# mount.net
KiCad netlist of a schematic drawn in EAGLE
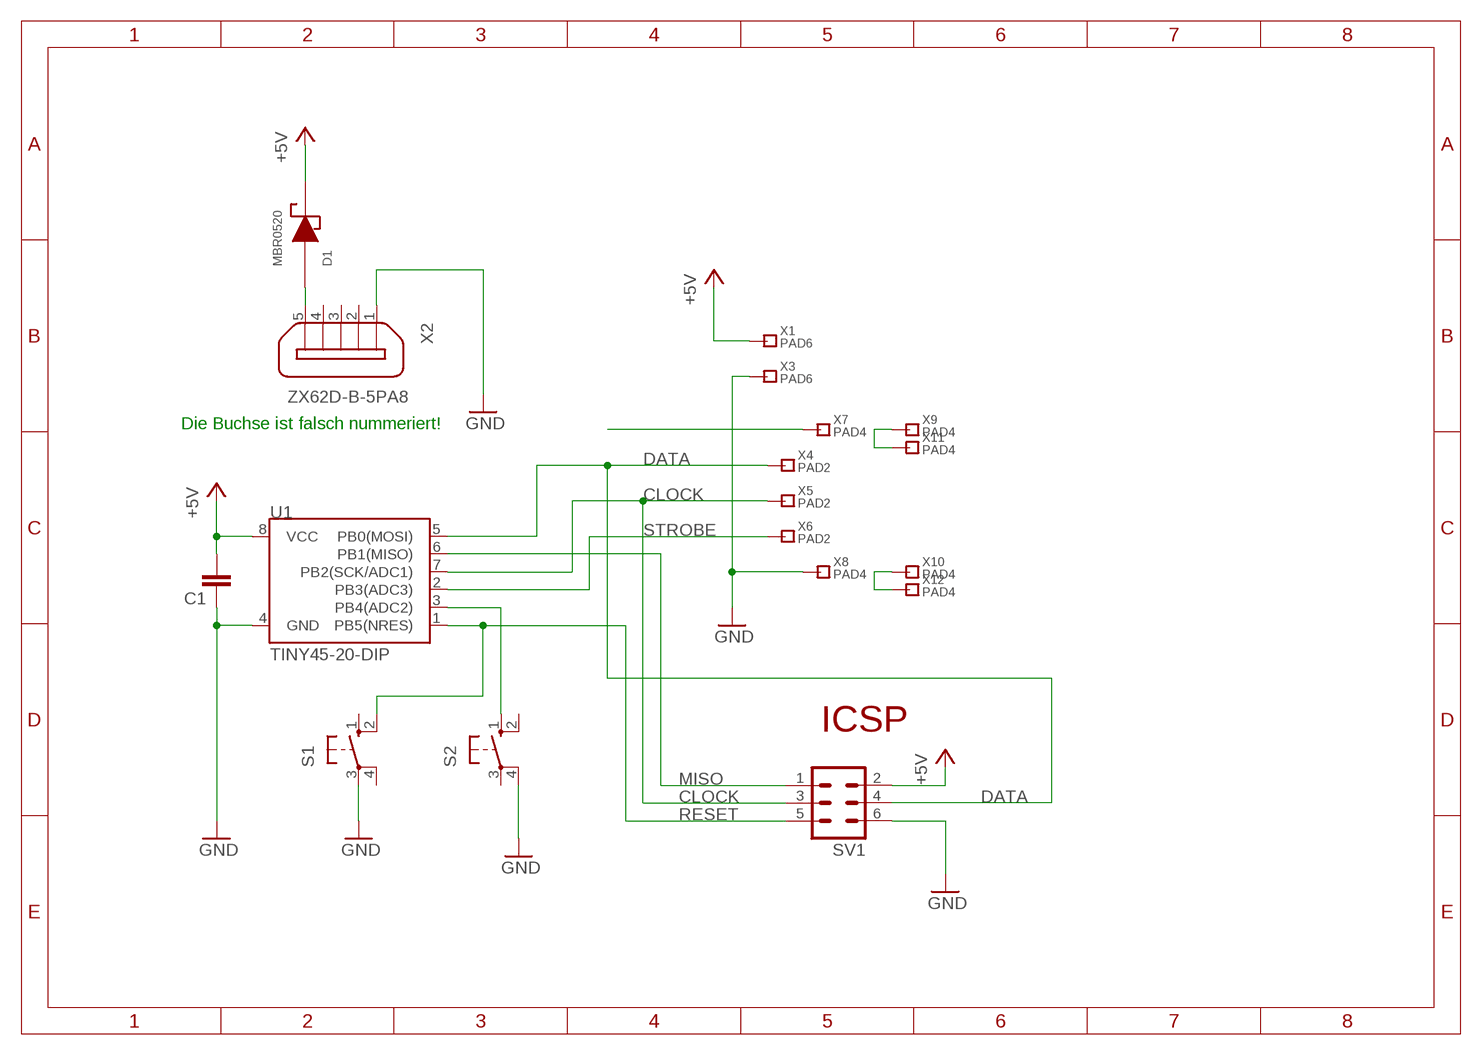
[diagram p0: schematic, sheet 1]

(export (version "E")
  (design (tool "Eeschema 10.0.6"))
  (components
    (comp (ref "C1")
      (value "C-EUC0805")
      (footprint "eagle-import:C0805")
      (libsource (lib "eagle-import") (part "C-EUC0805"))
    )
    (comp (ref "D1")
      (value "MBR0520")
      (footprint "eagle-import:SOD-123")
      (libsource (lib "eagle-import") (part "MBR0520"))
    )
    (comp (ref "S1")
      (value "10-XX")
      (footprint "eagle-import:B3F-10XX")
      (fields (field (name "MPN") "B3F-1000"))
      (libsource (lib "eagle-import") (part "10-XX"))
    )
    (comp (ref "S2")
      (value "10-XX")
      (footprint "eagle-import:B3F-10XX")
      (fields (field (name "MPN") "B3F-1000"))
      (libsource (lib "eagle-import") (part "10-XX"))
    )
    (comp (ref "SV1")
      (value "MA03-2")
      (footprint "eagle-import:MA03-2")
      (libsource (lib "eagle-import") (part "MA03-2"))
    )
    (comp (ref "U1")
      (value "TINY45-20-DIP")
      (footprint "eagle-import:DIP08_MCU")
      (libsource (lib "eagle-import") (part "ATTINY45TINY45-20-DIP"))
    )
    (comp (ref "X1")
      (value "PAD6")
      (footprint "eagle-import:SMDPAD")
      (libsource (lib "eagle-import") (part "PAD6"))
    )
    (comp (ref "X2")
      (value "ZX62D-B-5PA8")
      (footprint "eagle-import:ZX62D-B-5PA8")
      (fields (field (name "MF") "Hirose"))
      (libsource (lib "eagle-import") (part "ZX62D-B-5PA8"))
    )
    (comp (ref "X3")
      (value "PAD6")
      (footprint "eagle-import:SMDPAD")
      (libsource (lib "eagle-import") (part "PAD6"))
    )
    (comp (ref "X4")
      (value "PAD2")
      (footprint "eagle-import:SMDPAD_S")
      (libsource (lib "eagle-import") (part "PAD2"))
    )
    (comp (ref "X5")
      (value "PAD2")
      (footprint "eagle-import:SMDPAD_S")
      (libsource (lib "eagle-import") (part "PAD2"))
    )
    (comp (ref "X6")
      (value "PAD2")
      (footprint "eagle-import:SMDPAD_S")
      (libsource (lib "eagle-import") (part "PAD2"))
    )
    (comp (ref "X7")
      (value "PAD4")
      (footprint "eagle-import:SMDPAD_M")
      (libsource (lib "eagle-import") (part "PAD4"))
    )
    (comp (ref "X8")
      (value "PAD4")
      (footprint "eagle-import:SMDPAD_M")
      (libsource (lib "eagle-import") (part "PAD4"))
    )
    (comp (ref "X9")
      (value "PAD4")
      (footprint "eagle-import:SMDPAD_M")
      (libsource (lib "eagle-import") (part "PAD4"))
    )
    (comp (ref "X10")
      (value "PAD4")
      (footprint "eagle-import:SMDPAD_M")
      (libsource (lib "eagle-import") (part "PAD4"))
    )
    (comp (ref "X11")
      (value "PAD4")
      (footprint "eagle-import:SMDPAD_M")
      (libsource (lib "eagle-import") (part "PAD4"))
    )
    (comp (ref "X12")
      (value "PAD4")
      (footprint "eagle-import:SMDPAD_M")
      (libsource (lib "eagle-import") (part "PAD4"))
    )
  )
  (nets
    (net (code "1") (name "+5V") (class "Default")
      (node (ref "C1") (pin "2") (pinfunction "2_2") (pintype "passive"))
      (node (ref "D1") (pin "1") (pinfunction "CA_1") (pintype "passive"))
      (node (ref "SV1") (pin "2") (pinfunction "2_2") (pintype "passive"))
      (node (ref "U1") (pin "8") (pinfunction "VCC_8") (pintype "bidirectional"))
      (node (ref "X1") (pin "P$1") (pinfunction "P$1_P$1") (pintype "bidirectional"))
    )
    (net (code "2") (name "/CLOCK") (class "Default")
      (node (ref "SV1") (pin "3") (pinfunction "3_3") (pintype "passive"))
      (node (ref "U1") (pin "7") (pinfunction "PB2(SCK/ADC1)_7") (pintype "bidirectional"))
      (node (ref "X5") (pin "P$1") (pinfunction "P$1_P$1") (pintype "bidirectional"))
    )
    (net (code "3") (name "/DATA") (class "Default")
      (node (ref "SV1") (pin "4") (pinfunction "4_4") (pintype "passive"))
      (node (ref "U1") (pin "5") (pinfunction "PB0(MOSI)_5") (pintype "bidirectional"))
      (node (ref "X4") (pin "P$1") (pinfunction "P$1_P$1") (pintype "bidirectional"))
    )
    (net (code "4") (name "/MISO") (class "Default")
      (node (ref "SV1") (pin "1") (pinfunction "1_1") (pintype "passive"))
      (node (ref "U1") (pin "6") (pinfunction "PB1(MISO)_6") (pintype "bidirectional"))
    )
    (net (code "5") (name "/RESET") (class "Default")
      (node (ref "S1") (pin "2") (pinfunction "S1_2") (pintype "passive"))
      (node (ref "SV1") (pin "5") (pinfunction "5_5") (pintype "passive"))
      (node (ref "U1") (pin "1") (pinfunction "PB5(NRES)_1") (pintype "bidirectional"))
    )
    (net (code "6") (name "/STROBE") (class "Default")
      (node (ref "U1") (pin "2") (pinfunction "PB3(ADC3)_2") (pintype "bidirectional"))
      (node (ref "X6") (pin "P$1") (pinfunction "P$1_P$1") (pintype "bidirectional"))
    )
    (net (code "7") (name "GND") (class "Default")
      (node (ref "C1") (pin "1") (pinfunction "1_1") (pintype "passive"))
      (node (ref "S1") (pin "3") (pinfunction "P_3") (pintype "passive"))
      (node (ref "S2") (pin "4") (pinfunction "P1_4") (pintype "passive"))
      (node (ref "SV1") (pin "6") (pinfunction "6_6") (pintype "passive"))
      (node (ref "U1") (pin "4") (pinfunction "GND_4") (pintype "bidirectional"))
      (node (ref "X2") (pin "1") (pinfunction "1_1") (pintype "passive"))
      (node (ref "X3") (pin "P$1") (pinfunction "P$1_P$1") (pintype "bidirectional"))
      (node (ref "X8") (pin "P$1") (pinfunction "P$1_P$1") (pintype "bidirectional"))
    )
    (net (code "8") (name "Net-(D1-AN)") (class "Default")
      (node (ref "D1") (pin "2") (pinfunction "AN_2") (pintype "passive"))
      (node (ref "X2") (pin "5") (pinfunction "5_5") (pintype "passive"))
    )
    (net (code "9") (name "Net-(S2-S)") (class "Default")
      (node (ref "S2") (pin "1") (pinfunction "S_1") (pintype "passive"))
      (node (ref "U1") (pin "3") (pinfunction "PB4(ADC2)_3") (pintype "bidirectional"))
    )
    (net (code "10") (name "Net-(X10-PadP$1)") (class "Default")
      (node (ref "X10") (pin "P$1") (pinfunction "P$1_P$1") (pintype "bidirectional"))
      (node (ref "X12") (pin "P$1") (pinfunction "P$1_P$1") (pintype "bidirectional"))
    )
    (net (code "11") (name "Net-(X11-PadP$1)") (class "Default")
      (node (ref "X11") (pin "P$1") (pinfunction "P$1_P$1") (pintype "bidirectional"))
      (node (ref "X9") (pin "P$1") (pinfunction "P$1_P$1") (pintype "bidirectional"))
    )
    (net (code "12") (name "unconnected-(S1-P1-Pad4)") (class "Default")
      (node (ref "S1") (pin "4") (pinfunction "P1_4") (pintype "passive"))
    )
    (net (code "13") (name "unconnected-(S1-S-Pad1)") (class "Default")
      (node (ref "S1") (pin "1") (pinfunction "S_1") (pintype "passive"))
    )
    (net (code "14") (name "unconnected-(S2-P-Pad3)") (class "Default")
      (node (ref "S2") (pin "3") (pinfunction "P_3") (pintype "passive"))
    )
    (net (code "15") (name "unconnected-(S2-S1-Pad2)") (class "Default")
      (node (ref "S2") (pin "2") (pinfunction "S1_2") (pintype "passive"))
    )
    (net (code "16") (name "unconnected-(X2-Pad2)") (class "Default")
      (node (ref "X2") (pin "2") (pinfunction "2_2") (pintype "passive"))
    )
    (net (code "17") (name "unconnected-(X2-Pad3)") (class "Default")
      (node (ref "X2") (pin "3") (pinfunction "3_3") (pintype "passive"))
    )
    (net (code "18") (name "unconnected-(X2-Pad4)") (class "Default")
      (node (ref "X2") (pin "4") (pinfunction "4_4") (pintype "passive"))
    )
    (net (code "19") (name "unconnected-(X7-PadP$1)") (class "Default")
      (node (ref "X7") (pin "P$1") (pinfunction "P$1_P$1") (pintype "bidirectional"))
    )
  )
)
